# 2002_USB.net
KiCad netlist of a schematic drawn in Altium Designer
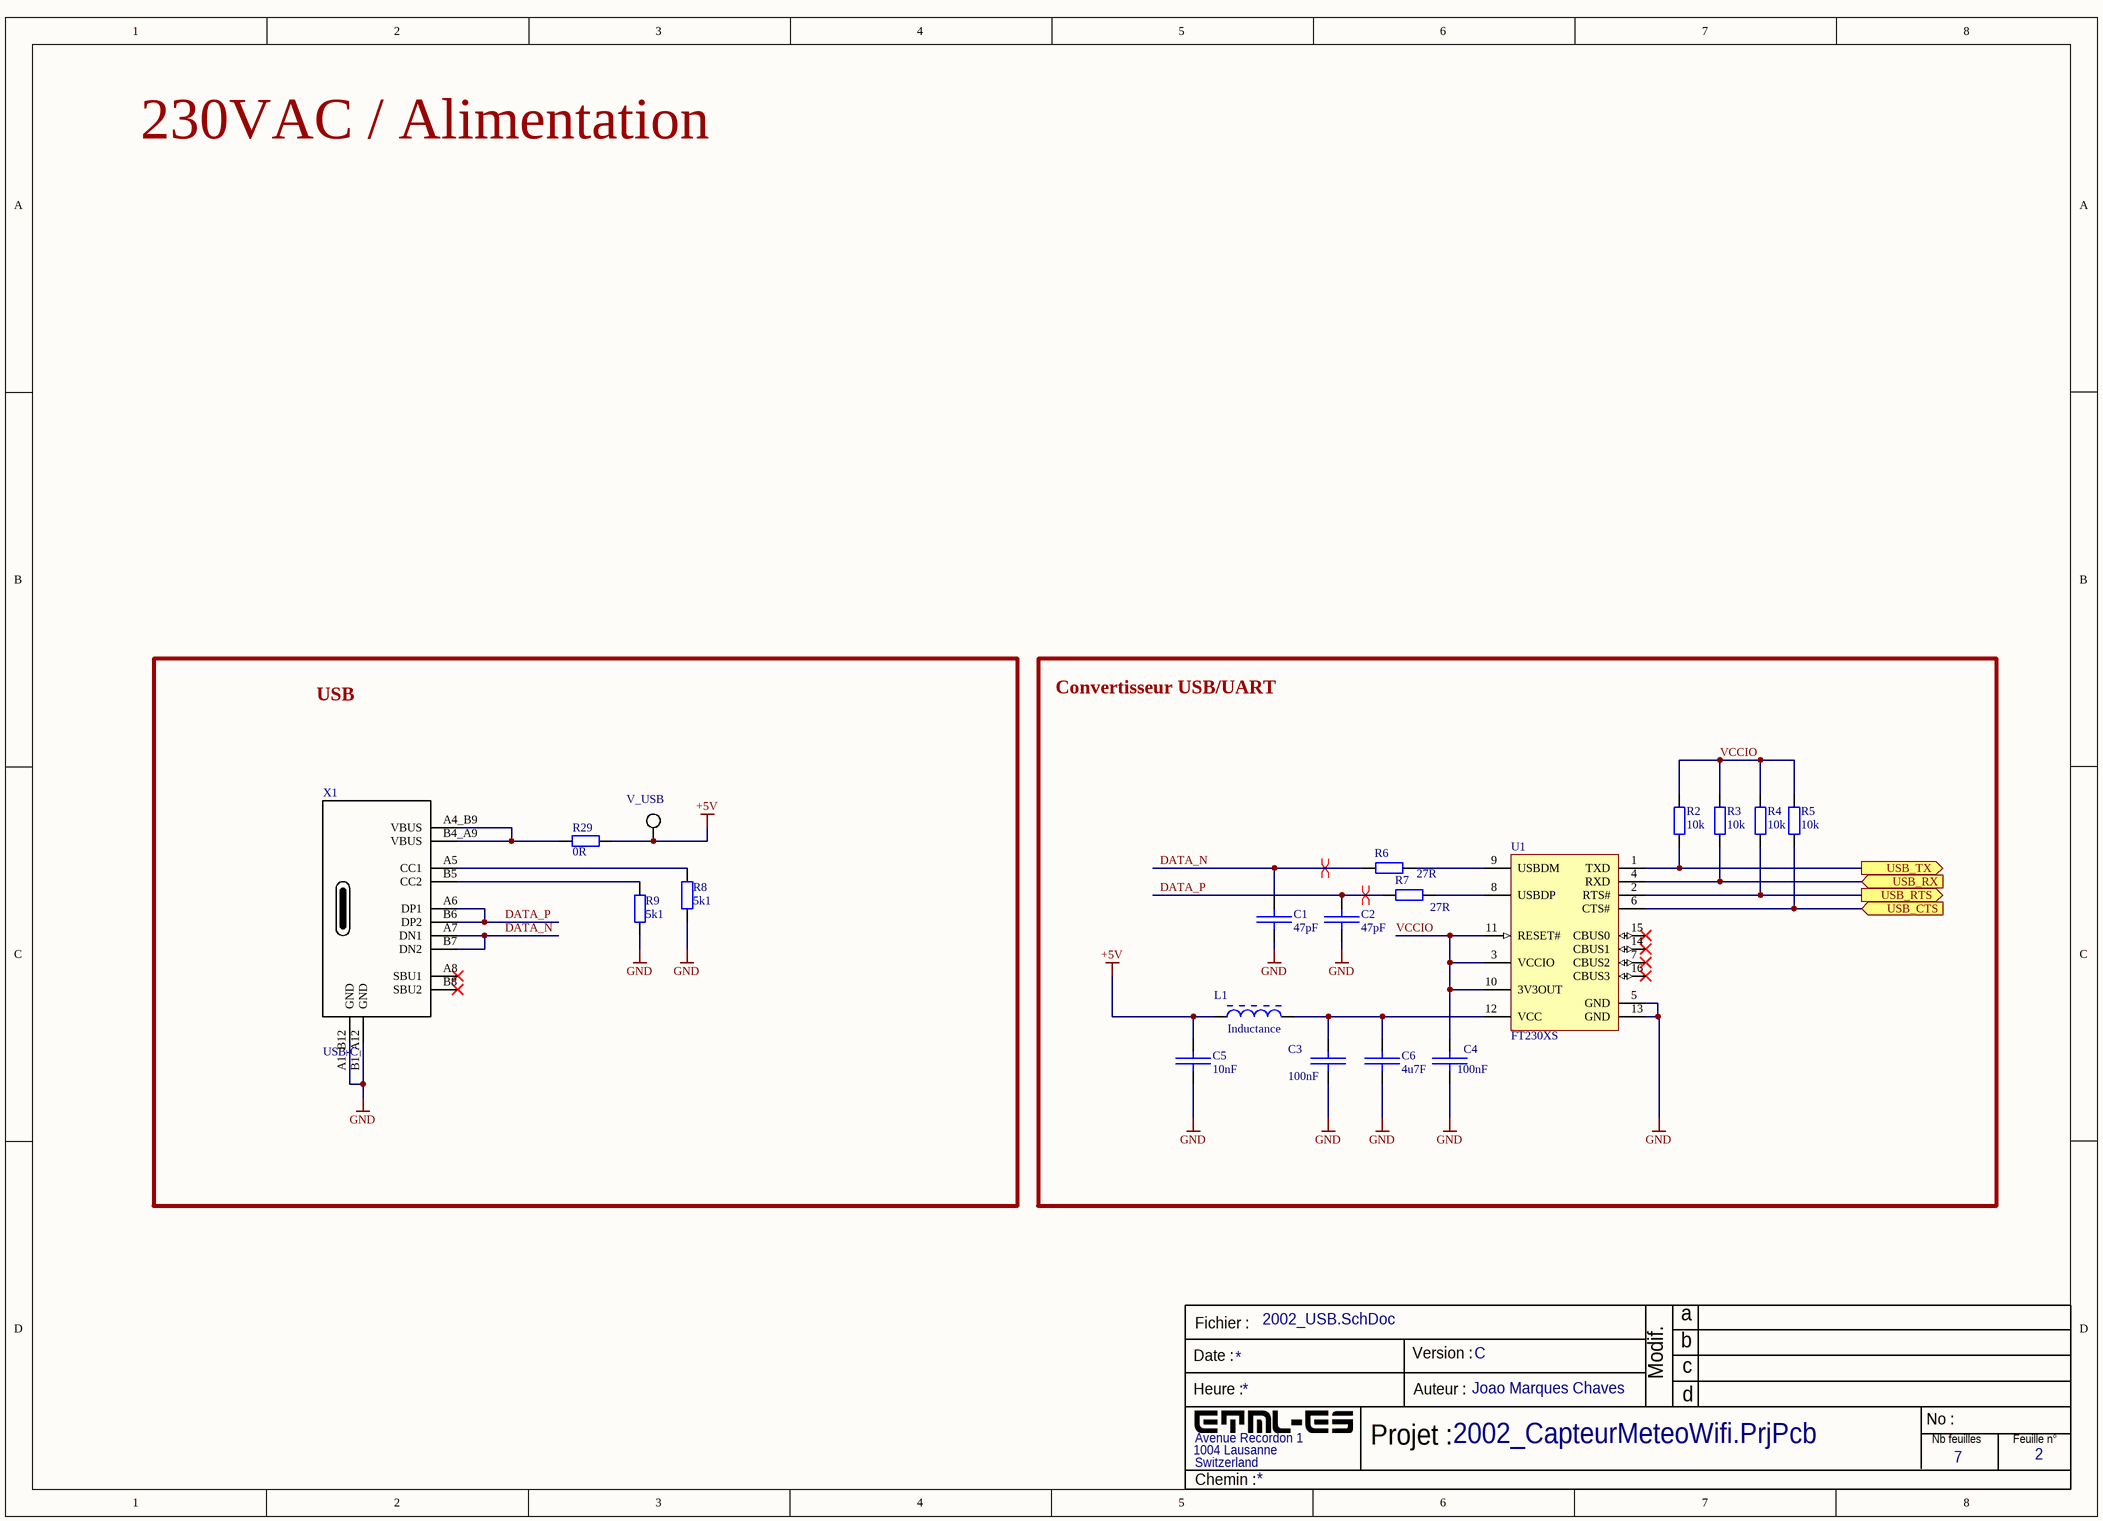
[diagram p0: 2002_USB.SchDoc]

(export (version "E")
  (design (tool "Eeschema 10.0.6"))
  (components
    (comp (ref "C1")
      (value "47pF")
      (footprint "0805")
      (description "Condensator")
      (libsource (lib "2002_CapteurMeteoWifi") (part "Condensator"))
    )
    (comp (ref "C2")
      (value "47pF")
      (footprint "0805")
      (description "Condensator")
      (libsource (lib "2002_CapteurMeteoWifi") (part "Condensator"))
    )
    (comp (ref "C3")
      (value "100nF")
      (footprint "0805")
      (description "0805 Condensator")
      (libsource (lib "2002_CapteurMeteoWifi") (part "Condensator"))
    )
    (comp (ref "C4")
      (value "100nF")
      (footprint "0805")
      (description "0805 Condensator")
      (libsource (lib "2002_CapteurMeteoWifi") (part "Condensator"))
    )
    (comp (ref "C5")
      (value "10nF")
      (footprint "0805")
      (description "0805 Condensator")
      (libsource (lib "2002_CapteurMeteoWifi") (part "Condensator"))
    )
    (comp (ref "C6")
      (value "4u7F")
      (footprint "0805")
      (description "0805 Condensator")
      (libsource (lib "2002_CapteurMeteoWifi") (part "Condensator"))
    )
    (comp (ref "L1")
      (value "Inductance")
      (footprint "FB_MI0805K601R-10")
      (description "MI0805K601R-10")
      (fields (field (name "MANUFACTURER") "Laird"))
      (libsource (lib "2002_CapteurMeteoWifi") (part "CMP-2000-05196-1"))
    )
    (comp (ref "R2")
      (value "10k")
      (footprint "0805")
      (description "SMD Resistor")
      (fields (field (name "RESISTANCE") "10k"))
      (libsource (lib "2312-MS-0805") (part "RES-0805"))
    )
    (comp (ref "R3")
      (value "10k")
      (footprint "0805")
      (description "SMD Resistor")
      (fields (field (name "RESISTANCE") "10k"))
      (libsource (lib "2312-MS-0805") (part "RES-0805"))
    )
    (comp (ref "R4")
      (value "10k")
      (footprint "0805")
      (description "SMD Resistor")
      (fields (field (name "RESISTANCE") "10k"))
      (libsource (lib "2312-MS-0805") (part "RES-0805"))
    )
    (comp (ref "R5")
      (value "10k")
      (footprint "0805")
      (description "SMD Resistor")
      (fields (field (name "RESISTANCE") "10k"))
      (libsource (lib "2312-MS-0805") (part "RES-0805"))
    )
    (comp (ref "R6")
      (value "27R")
      (footprint "0805")
      (description "SMD Resistor 0805, 330Ω")
      (fields (field (name "RESISTANCE") "27R"))
      (libsource (lib "2312-MS-0805") (part "RES-0805"))
    )
    (comp (ref "R7")
      (value "27R")
      (footprint "0805")
      (description "SMD Resistor 0805, 330Ω")
      (fields (field (name "RESISTANCE") "27R"))
      (libsource (lib "2312-MS-0805") (part "RES-0805"))
    )
    (comp (ref "R8")
      (value "5k1")
      (footprint "0805")
      (fields (field (name "PART NUMBER") "ERJ6ENF2703V") (field (name "MANUFACTURER") "Panasonic"))
      (libsource (lib "2121_Robot3roues_V2.0") (part "RES"))
    )
    (comp (ref "R9")
      (value "5k1")
      (footprint "0805")
      (fields (field (name "PART NUMBER") "ERJ6ENF2703V") (field (name "MANUFACTURER") "Panasonic"))
      (libsource (lib "2121_Robot3roues_V2.0") (part "RES"))
    )
    (comp (ref "R29")
      (value "0R")
      (footprint "0805")
      (description "Resistor")
      (fields (field (name "PUBLISHER") "Altium Limited"))
      (libsource (lib "2209_CommandeDomotiqueIR_1") (part "Res2_1"))
    )
    (comp (ref "U1")
      (value "FT230XS")
      (footprint "FTDI-SSOP-16_L")
      (description "USB to Basic UART IC, 2.97 to 5.5 V, -40 to 85 degC, 16-Pin SSOP, RoHS")
      (fields (field (name "MANUFACTURER") "FTDI"))
      (libsource (lib "Schlib1") (part "CMP-2000-06288-1"))
    )
    (comp (ref "V_USB")
      (value "5019")
      (footprint "TESTPOINT_SMD")
      (description "Test point smd")
      (libsource (lib "2002_CapteurMeteoWifi") (part "TESTPOINT"))
    )
    (comp (ref "X1")
      (value "USB-C")
      (footprint "GCT_USB4105-GF-A")
      (description "U262-161N-4BVC11")
      (libsource (lib "Schlib1") (part "USB-C Type 2.0"))
    )
  )
  (nets
    (net (code "1") (name "+5V") (class "Default")
      (node (ref "C5") (pin "1") (pinfunction "1_1") (pintype "passive"))
      (node (ref "L1") (pin "1") (pinfunction "1_1") (pintype "passive"))
      (node (ref "R29") (pin "2") (pinfunction "2_2") (pintype "passive"))
      (node (ref "V_USB") (pin "1") (pinfunction "1_1") (pintype "passive"))
    )
    (net (code "2") (name "/DATA_N") (class "Default")
      (node (ref "C1") (pin "1") (pinfunction "1_1") (pintype "passive"))
      (node (ref "R6") (pin "1") (pinfunction "1_1") (pintype "passive"))
      (node (ref "X1") (pin "A7") (pinfunction "DN1_A7") (pintype "passive"))
      (node (ref "X1") (pin "B7") (pinfunction "DN2_B7") (pintype "passive"))
    )
    (net (code "3") (name "/DATA_P") (class "Default")
      (node (ref "C2") (pin "1") (pinfunction "1_1") (pintype "passive"))
      (node (ref "R7") (pin "1") (pinfunction "1_1") (pintype "passive"))
      (node (ref "X1") (pin "A6") (pinfunction "DP1_A6") (pintype "passive"))
      (node (ref "X1") (pin "B6") (pinfunction "DP2_B6") (pintype "passive"))
    )
    (net (code "4") (name "/USB_CTS") (class "Default")
      (node (ref "R5") (pin "1") (pinfunction "1_1") (pintype "passive"))
      (node (ref "U1") (pin "6") (pinfunction "CTS#_6") (pintype "passive"))
    )
    (net (code "5") (name "/USB_RTS") (class "Default")
      (node (ref "R4") (pin "1") (pinfunction "1_1") (pintype "passive"))
      (node (ref "U1") (pin "2") (pinfunction "RTS#_2") (pintype "passive"))
    )
    (net (code "6") (name "/USB_RX") (class "Default")
      (node (ref "R3") (pin "1") (pinfunction "1_1") (pintype "passive"))
      (node (ref "U1") (pin "4") (pinfunction "RXD_4") (pintype "passive"))
    )
    (net (code "7") (name "/USB_TX") (class "Default")
      (node (ref "R2") (pin "1") (pinfunction "1_1") (pintype "passive"))
      (node (ref "U1") (pin "1") (pinfunction "TXD_1") (pintype "passive"))
    )
    (net (code "8") (name "/VCCIO") (class "Default")
      (node (ref "C4") (pin "1") (pinfunction "1_1") (pintype "passive"))
      (node (ref "R2") (pin "2") (pinfunction "2_2") (pintype "passive"))
      (node (ref "R3") (pin "2") (pinfunction "2_2") (pintype "passive"))
      (node (ref "R4") (pin "2") (pinfunction "2_2") (pintype "passive"))
      (node (ref "R5") (pin "2") (pinfunction "2_2") (pintype "passive"))
      (node (ref "U1") (pin "10") (pinfunction "3V3OUT_10") (pintype "power_in"))
      (node (ref "U1") (pin "11") (pinfunction "RESET#_11") (pintype "input"))
      (node (ref "U1") (pin "3") (pinfunction "VCCIO_3") (pintype "power_in"))
    )
    (net (code "9") (name "GND") (class "Default")
      (node (ref "C1") (pin "2") (pinfunction "2_2") (pintype "passive"))
      (node (ref "C2") (pin "2") (pinfunction "2_2") (pintype "passive"))
      (node (ref "C3") (pin "2") (pinfunction "2_2") (pintype "passive"))
      (node (ref "C4") (pin "2") (pinfunction "2_2") (pintype "passive"))
      (node (ref "C5") (pin "2") (pinfunction "2_2") (pintype "passive"))
      (node (ref "C6") (pin "2") (pinfunction "2_2") (pintype "passive"))
      (node (ref "R8") (pin "1") (pinfunction "1_1") (pintype "passive"))
      (node (ref "R9") (pin "1") (pinfunction "1_1") (pintype "passive"))
      (node (ref "U1") (pin "13") (pinfunction "GND_13") (pintype "power_in"))
      (node (ref "U1") (pin "5") (pinfunction "GND_5") (pintype "power_in"))
      (node (ref "X1") (pin "A1_B12") (pinfunction "GND_A1_B12") (pintype "passive"))
      (node (ref "X1") (pin "B1_A12") (pinfunction "GND_B1_A12") (pintype "passive"))
    )
    (net (code "10") (name "Net-(R29-Pad1)") (class "Default")
      (node (ref "R29") (pin "1") (pinfunction "1_1") (pintype "passive"))
      (node (ref "X1") (pin "A4_B9") (pinfunction "VBUS_A4_B9") (pintype "passive"))
      (node (ref "X1") (pin "B4_A9") (pinfunction "VBUS_B4_A9") (pintype "passive"))
    )
    (net (code "11") (name "Net-(U1-USBDM)") (class "Default")
      (node (ref "R6") (pin "2") (pinfunction "2_2") (pintype "passive"))
      (node (ref "U1") (pin "9") (pinfunction "USBDM_9") (pintype "passive"))
    )
    (net (code "12") (name "Net-(U1-USBDP)") (class "Default")
      (node (ref "R7") (pin "2") (pinfunction "2_2") (pintype "passive"))
      (node (ref "U1") (pin "8") (pinfunction "USBDP_8") (pintype "passive"))
    )
    (net (code "13") (name "Net-(U1-VCC)") (class "Default")
      (node (ref "C3") (pin "1") (pinfunction "1_1") (pintype "passive"))
      (node (ref "C6") (pin "1") (pinfunction "1_1") (pintype "passive"))
      (node (ref "L1") (pin "2") (pinfunction "2_2") (pintype "passive"))
      (node (ref "U1") (pin "12") (pinfunction "VCC_12") (pintype "power_in"))
    )
    (net (code "14") (name "Net-(X1-CC1)") (class "Default")
      (node (ref "R8") (pin "2") (pinfunction "2_2") (pintype "passive"))
      (node (ref "X1") (pin "A5") (pinfunction "CC1_A5") (pintype "passive"))
    )
    (net (code "15") (name "Net-(X1-CC2)") (class "Default")
      (node (ref "R9") (pin "2") (pinfunction "2_2") (pintype "passive"))
      (node (ref "X1") (pin "B5") (pinfunction "CC2_B5") (pintype "passive"))
    )
    (net (code "16") (name "unconnected-(U1-CBUS0-Pad15)") (class "Default")
      (node (ref "U1") (pin "15") (pinfunction "CBUS0_15") (pintype "bidirectional+no_connect"))
    )
    (net (code "17") (name "unconnected-(U1-CBUS1-Pad14)") (class "Default")
      (node (ref "U1") (pin "14") (pinfunction "CBUS1_14") (pintype "bidirectional+no_connect"))
    )
    (net (code "18") (name "unconnected-(U1-CBUS2-Pad7)") (class "Default")
      (node (ref "U1") (pin "7") (pinfunction "CBUS2_7") (pintype "bidirectional+no_connect"))
    )
    (net (code "19") (name "unconnected-(U1-CBUS3-Pad16)") (class "Default")
      (node (ref "U1") (pin "16") (pinfunction "CBUS3_16") (pintype "bidirectional+no_connect"))
    )
    (net (code "20") (name "unconnected-(X1-SBU1-PadA8)") (class "Default")
      (node (ref "X1") (pin "A8") (pinfunction "SBU1_A8") (pintype "passive+no_connect"))
    )
    (net (code "21") (name "unconnected-(X1-SBU2-PadB8)") (class "Default")
      (node (ref "X1") (pin "B8") (pinfunction "SBU2_B8") (pintype "passive+no_connect"))
    )
  )
)
